# CBM_TAPE_PI.net
KiCad netlist of a schematic drawn in EAGLE
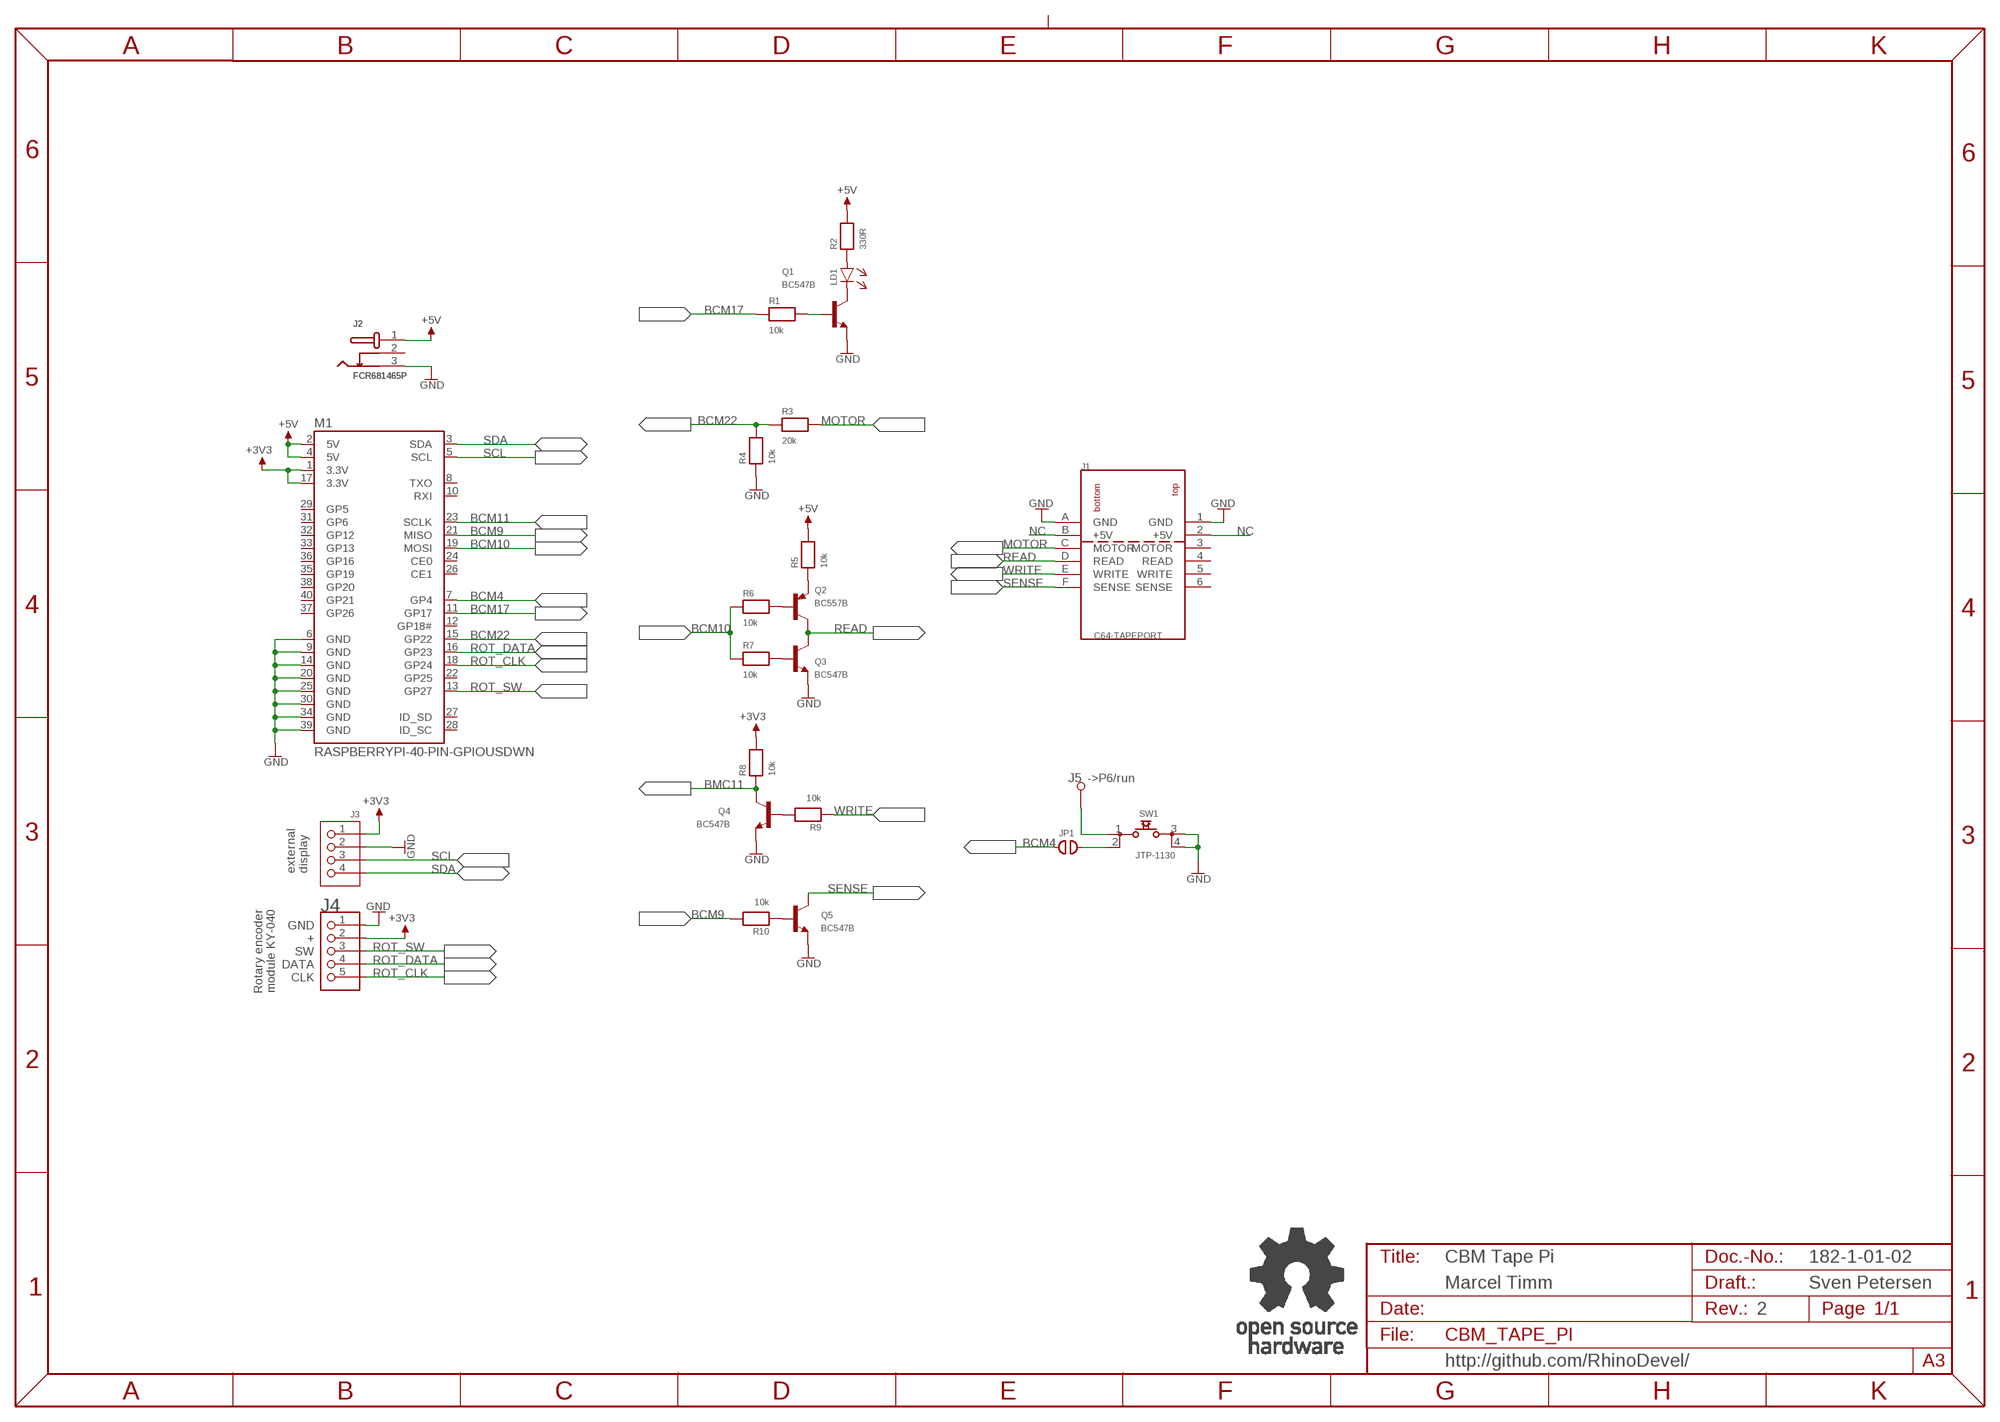
[diagram p0: schematic, sheet 1]

(export (version "E")
  (design (tool "Eeschema 10.0.6"))
  (components
    (comp (ref "J1")
      (value "C64-TAPEPORT")
      (footprint "eagle-import:TAPEPORT")
      (libsource (lib "eagle-import") (part "C64-TAPEPORT"))
    )
    (comp (ref "J2")
      (value "FCR681465P")
      (footprint "eagle-import:FCR681465P")
      (libsource (lib "eagle-import") (part "FCR681465P"))
    )
    (comp (ref "J3")
      (value "6410-4P")
      (footprint "eagle-import:6410-4P")
      (libsource (lib "eagle-import") (part "6410-4P"))
    )
    (comp (ref "J4")
      (value "6410-5P")
      (footprint "eagle-import:6410-5P")
      (libsource (lib "eagle-import") (part "6410-5P"))
    )
    (comp (ref "J5")
      (value "L1,2_R")
      (footprint "eagle-import:1,2MM_R")
      (libsource (lib "eagle-import") (part "L1,2_R"))
    )
    (comp (ref "JP1")
      (value "OPEN")
      (footprint "eagle-import:CP_OP")
      (libsource (lib "eagle-import") (part "OPEN"))
    )
    (comp (ref "LD1")
      (value "3MM")
      (footprint "eagle-import:3MM")
      (libsource (lib "eagle-import") (part "3MM"))
    )
    (comp (ref "M1")
      (value "RASPBERRYPI-40-PIN-GPIOUSDWN")
      (footprint "eagle-import:PI_HAT_40P_UPSIDEDOWN")
      (libsource (lib "eagle-import") (part "RASPBERRYPI-40-PIN-GPIOUSDWN"))
    )
    (comp (ref "Q1")
      (value "BC547B")
      (footprint "eagle-import:TO92")
      (libsource (lib "eagle-import") (part "BC547B"))
    )
    (comp (ref "Q2")
      (value "BC557B")
      (footprint "eagle-import:TO92-EBC")
      (libsource (lib "eagle-import") (part "BC557B"))
    )
    (comp (ref "Q3")
      (value "BC547B")
      (footprint "eagle-import:TO92")
      (libsource (lib "eagle-import") (part "BC547B"))
    )
    (comp (ref "Q4")
      (value "BC547B")
      (footprint "eagle-import:TO92")
      (libsource (lib "eagle-import") (part "BC547B"))
    )
    (comp (ref "Q5")
      (value "BC547B")
      (footprint "eagle-import:TO92")
      (libsource (lib "eagle-import") (part "BC547B"))
    )
    (comp (ref "R1")
      (value "10k")
      (footprint "eagle-import:R-10")
      (libsource (lib "eagle-import") (part "RES04"))
    )
    (comp (ref "R2")
      (value "330R")
      (footprint "eagle-import:R-10")
      (libsource (lib "eagle-import") (part "RES04"))
    )
    (comp (ref "R3")
      (value "20k")
      (footprint "eagle-import:R-10")
      (libsource (lib "eagle-import") (part "RES04"))
    )
    (comp (ref "R4")
      (value "10k")
      (footprint "eagle-import:R-10")
      (libsource (lib "eagle-import") (part "RES04"))
    )
    (comp (ref "R5")
      (value "10k")
      (footprint "eagle-import:R-10")
      (libsource (lib "eagle-import") (part "RES04"))
    )
    (comp (ref "R6")
      (value "10k")
      (footprint "eagle-import:R-10")
      (libsource (lib "eagle-import") (part "RES04"))
    )
    (comp (ref "R7")
      (value "10k")
      (footprint "eagle-import:R-10")
      (libsource (lib "eagle-import") (part "RES04"))
    )
    (comp (ref "R8")
      (value "10k")
      (footprint "eagle-import:R-10")
      (libsource (lib "eagle-import") (part "RES04"))
    )
    (comp (ref "R9")
      (value "10k")
      (footprint "eagle-import:R-10")
      (libsource (lib "eagle-import") (part "RES04"))
    )
    (comp (ref "R10")
      (value "10k")
      (footprint "eagle-import:R-10")
      (libsource (lib "eagle-import") (part "RES04"))
    )
    (comp (ref "SW1")
      (value "JTP-1130")
      (footprint "eagle-import:JTP-1130")
      (libsource (lib "eagle-import") (part "JTP-1130"))
    )
    (comp (ref "U$2")
      (value "OPEN_SOURCE_HW")
      (footprint "eagle-import:OPENHW")
      (libsource (lib "eagle-import") (part "OPEN_SOURCE_HW"))
    )
  )
  (nets
    (net (code "1") (name "+3V3") (class "Default")
      (node (ref "J3") (pin "1") (pinfunction "1_1") (pintype "passive"))
      (node (ref "J4") (pin "2") (pinfunction "2_2") (pintype "passive"))
      (node (ref "M1") (pin "1") (pinfunction "3.3V_1") (pintype "power_in"))
      (node (ref "M1") (pin "17") (pinfunction "3.3V_17") (pintype "power_in"))
      (node (ref "R8") (pin "2") (pinfunction "2_2") (pintype "passive"))
    )
    (net (code "2") (name "+5V") (class "Default")
      (node (ref "J2") (pin "1") (pinfunction "1_1") (pintype "bidirectional"))
      (node (ref "M1") (pin "2") (pinfunction "5V_2") (pintype "power_in"))
      (node (ref "M1") (pin "4") (pinfunction "5V_4") (pintype "power_in"))
      (node (ref "R2") (pin "2") (pinfunction "2_2") (pintype "passive"))
      (node (ref "R5") (pin "2") (pinfunction "2_2") (pintype "passive"))
    )
    (net (code "3") (name "/BCM4") (class "Default")
      (node (ref "JP1") (pin "1") (pinfunction "1_1") (pintype "passive"))
      (node (ref "M1") (pin "7") (pinfunction "GP4_7") (pintype "bidirectional"))
    )
    (net (code "4") (name "/BCM9") (class "Default")
      (node (ref "M1") (pin "21") (pinfunction "MISO_21") (pintype "input"))
      (node (ref "R10") (pin "2") (pinfunction "2_2") (pintype "passive"))
    )
    (net (code "5") (name "/BCM10") (class "Default")
      (node (ref "M1") (pin "19") (pinfunction "MOSI_19") (pintype "output"))
      (node (ref "R6") (pin "1") (pinfunction "1_1") (pintype "passive"))
      (node (ref "R7") (pin "1") (pinfunction "1_1") (pintype "passive"))
    )
    (net (code "6") (name "/BCM11") (class "Default")
      (node (ref "M1") (pin "23") (pinfunction "SCLK_23") (pintype "output"))
    )
    (net (code "7") (name "/BCM17") (class "Default")
      (node (ref "M1") (pin "11") (pinfunction "GP17_11") (pintype "bidirectional"))
      (node (ref "R1") (pin "1") (pinfunction "1_1") (pintype "passive"))
    )
    (net (code "8") (name "/BCM22") (class "Default")
      (node (ref "M1") (pin "15") (pinfunction "GP22_15") (pintype "bidirectional"))
      (node (ref "R3") (pin "1") (pinfunction "1_1") (pintype "passive"))
      (node (ref "R4") (pin "2") (pinfunction "2_2") (pintype "passive"))
    )
    (net (code "9") (name "/BMC11") (class "Default")
      (node (ref "Q4") (pin "3") (pinfunction "C_3") (pintype "passive"))
      (node (ref "R8") (pin "1") (pinfunction "1_1") (pintype "passive"))
    )
    (net (code "10") (name "/MOTOR") (class "Default")
      (node (ref "J1") (pin "C") (pinfunction "MOTOR_C") (pintype "output"))
      (node (ref "R3") (pin "2") (pinfunction "2_2") (pintype "passive"))
    )
    (net (code "11") (name "/NC") (class "Default")
      (node (ref "J1") (pin "2") (pinfunction "+5V_2") (pintype "power_in"))
      (node (ref "J1") (pin "B") (pinfunction "+5V_B") (pintype "power_in"))
    )
    (net (code "12") (name "/READ") (class "Default")
      (node (ref "J1") (pin "D") (pinfunction "READ_D") (pintype "input"))
      (node (ref "Q2") (pin "C") (pinfunction "C_C") (pintype "passive"))
      (node (ref "Q3") (pin "3") (pinfunction "C_3") (pintype "passive"))
    )
    (net (code "13") (name "/ROT_CLK") (class "Default")
      (node (ref "J4") (pin "5") (pinfunction "5_5") (pintype "passive"))
      (node (ref "M1") (pin "18") (pinfunction "GP24_18") (pintype "bidirectional"))
    )
    (net (code "14") (name "/ROT_DATA") (class "Default")
      (node (ref "J4") (pin "4") (pinfunction "4_4") (pintype "passive"))
      (node (ref "M1") (pin "16") (pinfunction "GP23_16") (pintype "bidirectional"))
    )
    (net (code "15") (name "/ROT_SW") (class "Default")
      (node (ref "J4") (pin "3") (pinfunction "3_3") (pintype "passive"))
      (node (ref "M1") (pin "13") (pinfunction "GP27_13") (pintype "bidirectional"))
    )
    (net (code "16") (name "/SCL") (class "Default")
      (node (ref "J3") (pin "3") (pinfunction "3_3") (pintype "passive"))
      (node (ref "M1") (pin "5") (pinfunction "SCL_5") (pintype "bidirectional"))
    )
    (net (code "17") (name "/SDA") (class "Default")
      (node (ref "J3") (pin "4") (pinfunction "4_4") (pintype "passive"))
      (node (ref "M1") (pin "3") (pinfunction "SDA_3") (pintype "bidirectional"))
    )
    (net (code "18") (name "/SENSE") (class "Default")
      (node (ref "J1") (pin "F") (pinfunction "SENSE_F") (pintype "input"))
      (node (ref "Q5") (pin "3") (pinfunction "C_3") (pintype "passive"))
    )
    (net (code "19") (name "/WRITE") (class "Default")
      (node (ref "J1") (pin "E") (pinfunction "WRITE_E") (pintype "output"))
      (node (ref "R9") (pin "1") (pinfunction "1_1") (pintype "passive"))
    )
    (net (code "20") (name "GND") (class "Default")
      (node (ref "J1") (pin "1") (pinfunction "GND_1") (pintype "power_in"))
      (node (ref "J1") (pin "A") (pinfunction "GND_A") (pintype "power_in"))
      (node (ref "J2") (pin "3") (pinfunction "3_3") (pintype "bidirectional"))
      (node (ref "J3") (pin "2") (pinfunction "2_2") (pintype "passive"))
      (node (ref "J4") (pin "1") (pinfunction "1_1") (pintype "passive"))
      (node (ref "M1") (pin "14") (pinfunction "GND_14") (pintype "power_in"))
      (node (ref "M1") (pin "20") (pinfunction "GND_20") (pintype "power_in"))
      (node (ref "M1") (pin "25") (pinfunction "GND_25") (pintype "power_in"))
      (node (ref "M1") (pin "30") (pinfunction "GND_30") (pintype "power_in"))
      (node (ref "M1") (pin "34") (pinfunction "GND_34") (pintype "power_in"))
      (node (ref "M1") (pin "39") (pinfunction "GND_39") (pintype "power_in"))
      (node (ref "M1") (pin "6") (pinfunction "GND_6") (pintype "power_in"))
      (node (ref "M1") (pin "9") (pinfunction "GND_9") (pintype "power_in"))
      (node (ref "Q1") (pin "1") (pinfunction "E_1") (pintype "passive"))
      (node (ref "Q3") (pin "1") (pinfunction "E_1") (pintype "passive"))
      (node (ref "Q4") (pin "1") (pinfunction "E_1") (pintype "passive"))
      (node (ref "Q5") (pin "1") (pinfunction "E_1") (pintype "passive"))
      (node (ref "R4") (pin "1") (pinfunction "1_1") (pintype "passive"))
      (node (ref "SW1") (pin "3") (pinfunction "3_3") (pintype "passive"))
      (node (ref "SW1") (pin "4") (pinfunction "4_4") (pintype "passive"))
    )
    (net (code "21") (name "Net-(J5-Pad1)") (class "Default")
      (node (ref "J5") (pin "1") (pinfunction "1_1") (pintype "passive"))
      (node (ref "SW1") (pin "1") (pinfunction "1_1") (pintype "passive"))
    )
    (net (code "22") (name "Net-(JP1-Pad2)") (class "Default")
      (node (ref "JP1") (pin "2") (pinfunction "2_2") (pintype "passive"))
      (node (ref "SW1") (pin "2") (pinfunction "2_2") (pintype "passive"))
    )
    (net (code "23") (name "Net-(LD1-K)") (class "Default")
      (node (ref "LD1") (pin "C") (pinfunction "K_C") (pintype "bidirectional"))
      (node (ref "Q1") (pin "3") (pinfunction "C_3") (pintype "passive"))
    )
    (net (code "24") (name "Net-(LD1-PadA)") (class "Default")
      (node (ref "LD1") (pin "A") (pinfunction "A_A") (pintype "bidirectional"))
      (node (ref "R2") (pin "1") (pinfunction "1_1") (pintype "passive"))
    )
    (net (code "25") (name "Net-(Q1-B)") (class "Default")
      (node (ref "Q1") (pin "2") (pinfunction "B_2") (pintype "passive"))
      (node (ref "R1") (pin "2") (pinfunction "2_2") (pintype "passive"))
    )
    (net (code "26") (name "Net-(Q2-PadB)") (class "Default")
      (node (ref "Q2") (pin "B") (pinfunction "B_B") (pintype "passive"))
      (node (ref "R6") (pin "2") (pinfunction "2_2") (pintype "passive"))
    )
    (net (code "27") (name "Net-(Q2-PadE)") (class "Default")
      (node (ref "Q2") (pin "E") (pinfunction "E_E") (pintype "passive"))
      (node (ref "R5") (pin "1") (pinfunction "1_1") (pintype "passive"))
    )
    (net (code "28") (name "Net-(Q3-B)") (class "Default")
      (node (ref "Q3") (pin "2") (pinfunction "B_2") (pintype "passive"))
      (node (ref "R7") (pin "2") (pinfunction "2_2") (pintype "passive"))
    )
    (net (code "29") (name "Net-(Q4-B)") (class "Default")
      (node (ref "Q4") (pin "2") (pinfunction "B_2") (pintype "passive"))
      (node (ref "R9") (pin "2") (pinfunction "2_2") (pintype "passive"))
    )
    (net (code "30") (name "Net-(Q5-B)") (class "Default")
      (node (ref "Q5") (pin "2") (pinfunction "B_2") (pintype "passive"))
      (node (ref "R10") (pin "1") (pinfunction "1_1") (pintype "passive"))
    )
    (net (code "31") (name "unconnected-(J1-MOTOR-Pad3)") (class "Default")
      (node (ref "J1") (pin "3") (pinfunction "MOTOR_3") (pintype "output"))
    )
    (net (code "32") (name "unconnected-(J1-READ-Pad4)") (class "Default")
      (node (ref "J1") (pin "4") (pinfunction "READ_4") (pintype "input"))
    )
    (net (code "33") (name "unconnected-(J1-SENSE-Pad6)") (class "Default")
      (node (ref "J1") (pin "6") (pinfunction "SENSE_6") (pintype "input"))
    )
    (net (code "34") (name "unconnected-(J1-WRITE-Pad5)") (class "Default")
      (node (ref "J1") (pin "5") (pinfunction "WRITE_5") (pintype "output"))
    )
    (net (code "35") (name "unconnected-(J2-Pad2)") (class "Default")
      (node (ref "J2") (pin "2") (pinfunction "2_2") (pintype "bidirectional"))
    )
    (net (code "36") (name "unconnected-(M1-CE0-Pad24)") (class "Default")
      (node (ref "M1") (pin "24") (pinfunction "CE0_24") (pintype "output"))
    )
    (net (code "37") (name "unconnected-(M1-CE1-Pad26)") (class "Default")
      (node (ref "M1") (pin "26") (pinfunction "CE1_26") (pintype "output"))
    )
    (net (code "38") (name "unconnected-(M1-GP5-Pad29)") (class "Default")
      (node (ref "M1") (pin "29") (pinfunction "GP5_29") (pintype "bidirectional"))
    )
    (net (code "39") (name "unconnected-(M1-GP6-Pad31)") (class "Default")
      (node (ref "M1") (pin "31") (pinfunction "GP6_31") (pintype "bidirectional"))
    )
    (net (code "40") (name "unconnected-(M1-GP12-Pad32)") (class "Default")
      (node (ref "M1") (pin "32") (pinfunction "GP12_32") (pintype "bidirectional"))
    )
    (net (code "41") (name "unconnected-(M1-GP13-Pad33)") (class "Default")
      (node (ref "M1") (pin "33") (pinfunction "GP13_33") (pintype "bidirectional"))
    )
    (net (code "42") (name "unconnected-(M1-GP16-Pad36)") (class "Default")
      (node (ref "M1") (pin "36") (pinfunction "GP16_36") (pintype "bidirectional"))
    )
    (net (code "43") (name "unconnected-(M1-GP18#-Pad12)") (class "Default")
      (node (ref "M1") (pin "12") (pinfunction "GP18#_12") (pintype "bidirectional"))
    )
    (net (code "44") (name "unconnected-(M1-GP19-Pad35)") (class "Default")
      (node (ref "M1") (pin "35") (pinfunction "GP19_35") (pintype "bidirectional"))
    )
    (net (code "45") (name "unconnected-(M1-GP20-Pad38)") (class "Default")
      (node (ref "M1") (pin "38") (pinfunction "GP20_38") (pintype "bidirectional"))
    )
    (net (code "46") (name "unconnected-(M1-GP21-Pad40)") (class "Default")
      (node (ref "M1") (pin "40") (pinfunction "GP21_40") (pintype "bidirectional"))
    )
    (net (code "47") (name "unconnected-(M1-GP25-Pad22)") (class "Default")
      (node (ref "M1") (pin "22") (pinfunction "GP25_22") (pintype "bidirectional"))
    )
    (net (code "48") (name "unconnected-(M1-GP26-Pad37)") (class "Default")
      (node (ref "M1") (pin "37") (pinfunction "GP26_37") (pintype "bidirectional"))
    )
    (net (code "49") (name "unconnected-(M1-ID_SC-Pad28)") (class "Default")
      (node (ref "M1") (pin "28") (pinfunction "ID_SC_28") (pintype "bidirectional"))
    )
    (net (code "50") (name "unconnected-(M1-ID_SD-Pad27)") (class "Default")
      (node (ref "M1") (pin "27") (pinfunction "ID_SD_27") (pintype "bidirectional"))
    )
    (net (code "51") (name "unconnected-(M1-RXI-Pad10)") (class "Default")
      (node (ref "M1") (pin "10") (pinfunction "RXI_10") (pintype "input"))
    )
    (net (code "52") (name "unconnected-(M1-TXO-Pad8)") (class "Default")
      (node (ref "M1") (pin "8") (pinfunction "TXO_8") (pintype "output"))
    )
  )
)
